# Adafruit_NeoPixel_Ring_60_Quarter.net
KiCad netlist of a schematic drawn in EAGLE
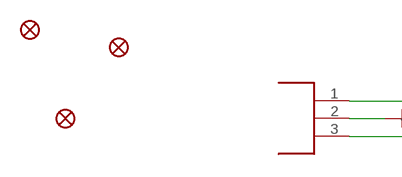
[diagram p0: schematic, sheet 1, part 1 of 2]
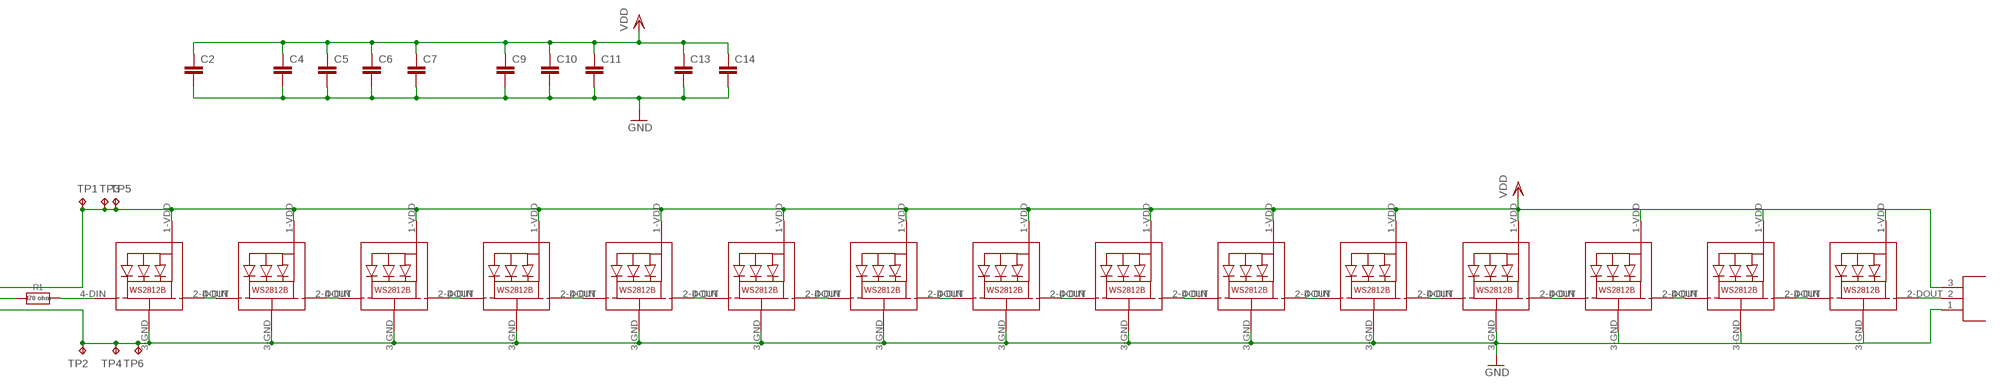
[diagram p1: schematic, sheet 1, part 2 of 2]

(export (version "E")
  (design (tool "Eeschema 10.0.6"))
  (components
    (comp (ref "C2")
      (value "C-EUC0603")
      (footprint "eagle-import:C0603")
      (libsource (lib "eagle-import") (part "C-EUC0603"))
    )
    (comp (ref "C4")
      (value "C-EUC0603")
      (footprint "eagle-import:C0603")
      (libsource (lib "eagle-import") (part "C-EUC0603"))
    )
    (comp (ref "C5")
      (value "C-EUC0603")
      (footprint "eagle-import:C0603")
      (libsource (lib "eagle-import") (part "C-EUC0603"))
    )
    (comp (ref "C6")
      (value "C-EUC0603")
      (footprint "eagle-import:C0603")
      (libsource (lib "eagle-import") (part "C-EUC0603"))
    )
    (comp (ref "C7")
      (value "C-EUC0603")
      (footprint "eagle-import:C0603")
      (libsource (lib "eagle-import") (part "C-EUC0603"))
    )
    (comp (ref "C9")
      (value "C-EUC0603")
      (footprint "eagle-import:C0603")
      (libsource (lib "eagle-import") (part "C-EUC0603"))
    )
    (comp (ref "C10")
      (value "C-EUC0603")
      (footprint "eagle-import:C0603")
      (libsource (lib "eagle-import") (part "C-EUC0603"))
    )
    (comp (ref "C11")
      (value "C-EUC0603")
      (footprint "eagle-import:C0603")
      (libsource (lib "eagle-import") (part "C-EUC0603"))
    )
    (comp (ref "C13")
      (value "C-EUC0603")
      (footprint "eagle-import:C0603")
      (libsource (lib "eagle-import") (part "C-EUC0603"))
    )
    (comp (ref "C14")
      (value "C-EUC0603")
      (footprint "eagle-import:C0603")
      (libsource (lib "eagle-import") (part "C-EUC0603"))
    )
    (comp (ref "FID1")
      (value "FIDUCIAL\"\"")
      (footprint "eagle-import:FIDUCIAL_1MM")
      (libsource (lib "eagle-import") (part "FIDUCIAL{dblquote}{dblquote}"))
    )
    (comp (ref "FID2")
      (value "FIDUCIAL\"\"")
      (footprint "eagle-import:FIDUCIAL_1MM")
      (libsource (lib "eagle-import") (part "FIDUCIAL{dblquote}{dblquote}"))
    )
    (comp (ref "FID3")
      (value "FIDUCIAL\"\"")
      (footprint "eagle-import:FIDUCIAL_1MM")
      (libsource (lib "eagle-import") (part "FIDUCIAL{dblquote}{dblquote}"))
    )
    (comp (ref "LED1")
      (value "WS2812B5050-NARROW")
      (footprint "eagle-import:WS2812B-NARROW")
      (libsource (lib "eagle-import") (part "WS2812B5050-NARROW"))
    )
    (comp (ref "LED2")
      (value "WS2812B5050-NARROW")
      (footprint "eagle-import:WS2812B-NARROW")
      (libsource (lib "eagle-import") (part "WS2812B5050-NARROW"))
    )
    (comp (ref "LED3")
      (value "WS2812B5050-NARROW")
      (footprint "eagle-import:WS2812B-NARROW")
      (libsource (lib "eagle-import") (part "WS2812B5050-NARROW"))
    )
    (comp (ref "LED4")
      (value "WS2812B5050-NARROW")
      (footprint "eagle-import:WS2812B-NARROW")
      (libsource (lib "eagle-import") (part "WS2812B5050-NARROW"))
    )
    (comp (ref "LED5")
      (value "WS2812B5050-NARROW")
      (footprint "eagle-import:WS2812B-NARROW")
      (libsource (lib "eagle-import") (part "WS2812B5050-NARROW"))
    )
    (comp (ref "LED6")
      (value "WS2812B5050-NARROW")
      (footprint "eagle-import:WS2812B-NARROW")
      (libsource (lib "eagle-import") (part "WS2812B5050-NARROW"))
    )
    (comp (ref "LED7")
      (value "WS2812B5050-NARROW")
      (footprint "eagle-import:WS2812B-NARROW")
      (libsource (lib "eagle-import") (part "WS2812B5050-NARROW"))
    )
    (comp (ref "LED8")
      (value "WS2812B5050-NARROW")
      (footprint "eagle-import:WS2812B-NARROW")
      (libsource (lib "eagle-import") (part "WS2812B5050-NARROW"))
    )
    (comp (ref "LED9")
      (value "WS2812B5050-NARROW")
      (footprint "eagle-import:WS2812B-NARROW")
      (libsource (lib "eagle-import") (part "WS2812B5050-NARROW"))
    )
    (comp (ref "LED10")
      (value "WS2812B5050-NARROW")
      (footprint "eagle-import:WS2812B-NARROW")
      (libsource (lib "eagle-import") (part "WS2812B5050-NARROW"))
    )
    (comp (ref "LED11")
      (value "WS2812B5050-NARROW")
      (footprint "eagle-import:WS2812B-NARROW")
      (libsource (lib "eagle-import") (part "WS2812B5050-NARROW"))
    )
    (comp (ref "LED12")
      (value "WS2812B5050-NARROW")
      (footprint "eagle-import:WS2812B-NARROW")
      (libsource (lib "eagle-import") (part "WS2812B5050-NARROW"))
    )
    (comp (ref "LED13")
      (value "WS2812B5050-NARROW")
      (footprint "eagle-import:WS2812B-NARROW")
      (libsource (lib "eagle-import") (part "WS2812B5050-NARROW"))
    )
    (comp (ref "LED14")
      (value "WS2812B5050-NARROW")
      (footprint "eagle-import:WS2812B-NARROW")
      (libsource (lib "eagle-import") (part "WS2812B5050-NARROW"))
    )
    (comp (ref "LED15")
      (value "WS2812B5050-NARROW")
      (footprint "eagle-import:WS2812B-NARROW")
      (libsource (lib "eagle-import") (part "WS2812B5050-NARROW"))
    )
    (comp (ref "R1")
      (value "470 ohm")
      (footprint "eagle-import:0603-NO")
      (libsource (lib "eagle-import") (part "RESISTOR_0603_NOOUT"))
    )
    (comp (ref "TP1")
      (value "TPTP20R")
      (footprint "eagle-import:TP20R")
      (libsource (lib "eagle-import") (part "TPTP20R"))
    )
    (comp (ref "TP2")
      (value "TPTP20R")
      (footprint "eagle-import:TP20R")
      (libsource (lib "eagle-import") (part "TPTP20R"))
    )
    (comp (ref "TP3")
      (value "TPTP20R")
      (footprint "eagle-import:TP20R")
      (libsource (lib "eagle-import") (part "TPTP20R"))
    )
    (comp (ref "TP4")
      (value "TPTP20R")
      (footprint "eagle-import:TP20R")
      (libsource (lib "eagle-import") (part "TPTP20R"))
    )
    (comp (ref "TP5")
      (value "TPTP20R")
      (footprint "eagle-import:TP20R")
      (libsource (lib "eagle-import") (part "TPTP20R"))
    )
    (comp (ref "TP6")
      (value "TPTP20R")
      (footprint "eagle-import:TP20R")
      (libsource (lib "eagle-import") (part "TPTP20R"))
    )
    (comp (ref "U$1")
      (value "RING_END_CONN_X3")
      (footprint "eagle-import:RING_END_CONN_X3")
      (libsource (lib "eagle-import") (part "RING_END_CONN_X3"))
    )
    (comp (ref "U$2")
      (value "RING_END_CONN_X3")
      (footprint "eagle-import:RING_END_CONN_X3")
      (libsource (lib "eagle-import") (part "RING_END_CONN_X3"))
    )
  )
  (nets
    (net (code "1") (name "GND") (class "Default")
      (node (ref "C10") (pin "2") (pinfunction "2_2") (pintype "passive"))
      (node (ref "C11") (pin "2") (pinfunction "2_2") (pintype "passive"))
      (node (ref "C13") (pin "2") (pinfunction "2_2") (pintype "passive"))
      (node (ref "C14") (pin "2") (pinfunction "2_2") (pintype "passive"))
      (node (ref "C2") (pin "2") (pinfunction "2_2") (pintype "passive"))
      (node (ref "C4") (pin "2") (pinfunction "2_2") (pintype "passive"))
      (node (ref "C5") (pin "2") (pinfunction "2_2") (pintype "passive"))
      (node (ref "C6") (pin "2") (pinfunction "2_2") (pintype "passive"))
      (node (ref "C7") (pin "2") (pinfunction "2_2") (pintype "passive"))
      (node (ref "C9") (pin "2") (pinfunction "2_2") (pintype "passive"))
      (node (ref "LED1") (pin "3-GND") (pinfunction "GND_3-GND") (pintype "power_in"))
      (node (ref "LED10") (pin "3-GND") (pinfunction "GND_3-GND") (pintype "power_in"))
      (node (ref "LED11") (pin "3-GND") (pinfunction "GND_3-GND") (pintype "power_in"))
      (node (ref "LED12") (pin "3-GND") (pinfunction "GND_3-GND") (pintype "power_in"))
      (node (ref "LED13") (pin "3-GND") (pinfunction "GND_3-GND") (pintype "power_in"))
      (node (ref "LED14") (pin "3-GND") (pinfunction "GND_3-GND") (pintype "power_in"))
      (node (ref "LED15") (pin "3-GND") (pinfunction "GND_3-GND") (pintype "power_in"))
      (node (ref "LED2") (pin "3-GND") (pinfunction "GND_3-GND") (pintype "power_in"))
      (node (ref "LED3") (pin "3-GND") (pinfunction "GND_3-GND") (pintype "power_in"))
      (node (ref "LED4") (pin "3-GND") (pinfunction "GND_3-GND") (pintype "power_in"))
      (node (ref "LED5") (pin "3-GND") (pinfunction "GND_3-GND") (pintype "power_in"))
      (node (ref "LED6") (pin "3-GND") (pinfunction "GND_3-GND") (pintype "power_in"))
      (node (ref "LED7") (pin "3-GND") (pinfunction "GND_3-GND") (pintype "power_in"))
      (node (ref "LED8") (pin "3-GND") (pinfunction "GND_3-GND") (pintype "power_in"))
      (node (ref "LED9") (pin "3-GND") (pinfunction "GND_3-GND") (pintype "power_in"))
      (node (ref "TP2") (pin "TP") (pinfunction "TP_TP") (pintype "input"))
      (node (ref "TP4") (pin "TP") (pinfunction "TP_TP") (pintype "input"))
      (node (ref "TP6") (pin "TP") (pinfunction "TP_TP") (pintype "input"))
      (node (ref "U$1") (pin "3") (pinfunction "P$3_3") (pintype "bidirectional"))
      (node (ref "U$2") (pin "1") (pinfunction "P$1_1") (pintype "bidirectional"))
    )
    (net (code "2") (name "Net-(LED1-DI)") (class "Default")
      (node (ref "LED1") (pin "4-DIN") (pinfunction "DI_4-DIN") (pintype "input"))
      (node (ref "R1") (pin "2") (pinfunction "2_2") (pintype "passive"))
    )
    (net (code "3") (name "Net-(LED1-DO)") (class "Default")
      (node (ref "LED1") (pin "2-DOUT") (pinfunction "DO_2-DOUT") (pintype "output"))
      (node (ref "LED2") (pin "4-DIN") (pinfunction "DI_4-DIN") (pintype "input"))
    )
    (net (code "4") (name "Net-(LED2-DO)") (class "Default")
      (node (ref "LED2") (pin "2-DOUT") (pinfunction "DO_2-DOUT") (pintype "output"))
      (node (ref "LED3") (pin "4-DIN") (pinfunction "DI_4-DIN") (pintype "input"))
    )
    (net (code "5") (name "Net-(LED3-DO)") (class "Default")
      (node (ref "LED3") (pin "2-DOUT") (pinfunction "DO_2-DOUT") (pintype "output"))
      (node (ref "LED4") (pin "4-DIN") (pinfunction "DI_4-DIN") (pintype "input"))
    )
    (net (code "6") (name "Net-(LED4-DO)") (class "Default")
      (node (ref "LED4") (pin "2-DOUT") (pinfunction "DO_2-DOUT") (pintype "output"))
      (node (ref "LED5") (pin "4-DIN") (pinfunction "DI_4-DIN") (pintype "input"))
    )
    (net (code "7") (name "Net-(LED5-DO)") (class "Default")
      (node (ref "LED5") (pin "2-DOUT") (pinfunction "DO_2-DOUT") (pintype "output"))
      (node (ref "LED6") (pin "4-DIN") (pinfunction "DI_4-DIN") (pintype "input"))
    )
    (net (code "8") (name "Net-(LED6-DO)") (class "Default")
      (node (ref "LED6") (pin "2-DOUT") (pinfunction "DO_2-DOUT") (pintype "output"))
      (node (ref "LED7") (pin "4-DIN") (pinfunction "DI_4-DIN") (pintype "input"))
    )
    (net (code "9") (name "Net-(LED7-DO)") (class "Default")
      (node (ref "LED7") (pin "2-DOUT") (pinfunction "DO_2-DOUT") (pintype "output"))
      (node (ref "LED8") (pin "4-DIN") (pinfunction "DI_4-DIN") (pintype "input"))
    )
    (net (code "10") (name "Net-(LED8-DO)") (class "Default")
      (node (ref "LED8") (pin "2-DOUT") (pinfunction "DO_2-DOUT") (pintype "output"))
      (node (ref "LED9") (pin "4-DIN") (pinfunction "DI_4-DIN") (pintype "input"))
    )
    (net (code "11") (name "Net-(LED10-DI)") (class "Default")
      (node (ref "LED10") (pin "4-DIN") (pinfunction "DI_4-DIN") (pintype "input"))
      (node (ref "LED9") (pin "2-DOUT") (pinfunction "DO_2-DOUT") (pintype "output"))
    )
    (net (code "12") (name "Net-(LED10-DO)") (class "Default")
      (node (ref "LED10") (pin "2-DOUT") (pinfunction "DO_2-DOUT") (pintype "output"))
      (node (ref "LED11") (pin "4-DIN") (pinfunction "DI_4-DIN") (pintype "input"))
    )
    (net (code "13") (name "Net-(LED11-DO)") (class "Default")
      (node (ref "LED11") (pin "2-DOUT") (pinfunction "DO_2-DOUT") (pintype "output"))
      (node (ref "LED12") (pin "4-DIN") (pinfunction "DI_4-DIN") (pintype "input"))
    )
    (net (code "14") (name "Net-(LED12-DO)") (class "Default")
      (node (ref "LED12") (pin "2-DOUT") (pinfunction "DO_2-DOUT") (pintype "output"))
      (node (ref "LED13") (pin "4-DIN") (pinfunction "DI_4-DIN") (pintype "input"))
    )
    (net (code "15") (name "Net-(LED13-DO)") (class "Default")
      (node (ref "LED13") (pin "2-DOUT") (pinfunction "DO_2-DOUT") (pintype "output"))
      (node (ref "LED14") (pin "4-DIN") (pinfunction "DI_4-DIN") (pintype "input"))
    )
    (net (code "16") (name "Net-(LED14-DO)") (class "Default")
      (node (ref "LED14") (pin "2-DOUT") (pinfunction "DO_2-DOUT") (pintype "output"))
      (node (ref "LED15") (pin "4-DIN") (pinfunction "DI_4-DIN") (pintype "input"))
    )
    (net (code "17") (name "Net-(LED15-DO)") (class "Default")
      (node (ref "LED15") (pin "2-DOUT") (pinfunction "DO_2-DOUT") (pintype "output"))
      (node (ref "U$2") (pin "2") (pinfunction "P$2_2") (pintype "bidirectional"))
    )
    (net (code "18") (name "Net-(U$1-P$2)") (class "Default")
      (node (ref "R1") (pin "1") (pinfunction "1_1") (pintype "passive"))
      (node (ref "U$1") (pin "2") (pinfunction "P$2_2") (pintype "bidirectional"))
    )
    (net (code "19") (name "VDD") (class "Default")
      (node (ref "C10") (pin "1") (pinfunction "1_1") (pintype "passive"))
      (node (ref "C11") (pin "1") (pinfunction "1_1") (pintype "passive"))
      (node (ref "C13") (pin "1") (pinfunction "1_1") (pintype "passive"))
      (node (ref "C14") (pin "1") (pinfunction "1_1") (pintype "passive"))
      (node (ref "C2") (pin "1") (pinfunction "1_1") (pintype "passive"))
      (node (ref "C4") (pin "1") (pinfunction "1_1") (pintype "passive"))
      (node (ref "C5") (pin "1") (pinfunction "1_1") (pintype "passive"))
      (node (ref "C6") (pin "1") (pinfunction "1_1") (pintype "passive"))
      (node (ref "C7") (pin "1") (pinfunction "1_1") (pintype "passive"))
      (node (ref "C9") (pin "1") (pinfunction "1_1") (pintype "passive"))
      (node (ref "LED1") (pin "1-VDD") (pinfunction "VDD_1-VDD") (pintype "power_in"))
      (node (ref "LED10") (pin "1-VDD") (pinfunction "VDD_1-VDD") (pintype "power_in"))
      (node (ref "LED11") (pin "1-VDD") (pinfunction "VDD_1-VDD") (pintype "power_in"))
      (node (ref "LED12") (pin "1-VDD") (pinfunction "VDD_1-VDD") (pintype "power_in"))
      (node (ref "LED13") (pin "1-VDD") (pinfunction "VDD_1-VDD") (pintype "power_in"))
      (node (ref "LED14") (pin "1-VDD") (pinfunction "VDD_1-VDD") (pintype "power_in"))
      (node (ref "LED15") (pin "1-VDD") (pinfunction "VDD_1-VDD") (pintype "power_in"))
      (node (ref "LED2") (pin "1-VDD") (pinfunction "VDD_1-VDD") (pintype "power_in"))
      (node (ref "LED3") (pin "1-VDD") (pinfunction "VDD_1-VDD") (pintype "power_in"))
      (node (ref "LED4") (pin "1-VDD") (pinfunction "VDD_1-VDD") (pintype "power_in"))
      (node (ref "LED5") (pin "1-VDD") (pinfunction "VDD_1-VDD") (pintype "power_in"))
      (node (ref "LED6") (pin "1-VDD") (pinfunction "VDD_1-VDD") (pintype "power_in"))
      (node (ref "LED7") (pin "1-VDD") (pinfunction "VDD_1-VDD") (pintype "power_in"))
      (node (ref "LED8") (pin "1-VDD") (pinfunction "VDD_1-VDD") (pintype "power_in"))
      (node (ref "LED9") (pin "1-VDD") (pinfunction "VDD_1-VDD") (pintype "power_in"))
      (node (ref "TP1") (pin "TP") (pinfunction "TP_TP") (pintype "input"))
      (node (ref "TP3") (pin "TP") (pinfunction "TP_TP") (pintype "input"))
      (node (ref "TP5") (pin "TP") (pinfunction "TP_TP") (pintype "input"))
      (node (ref "U$1") (pin "1") (pinfunction "P$1_1") (pintype "bidirectional"))
      (node (ref "U$2") (pin "3") (pinfunction "P$3_3") (pintype "bidirectional"))
    )
  )
)
